# JLink_ARM-OB_072_Sch.net
KiCad netlist of a schematic drawn in Altium Designer
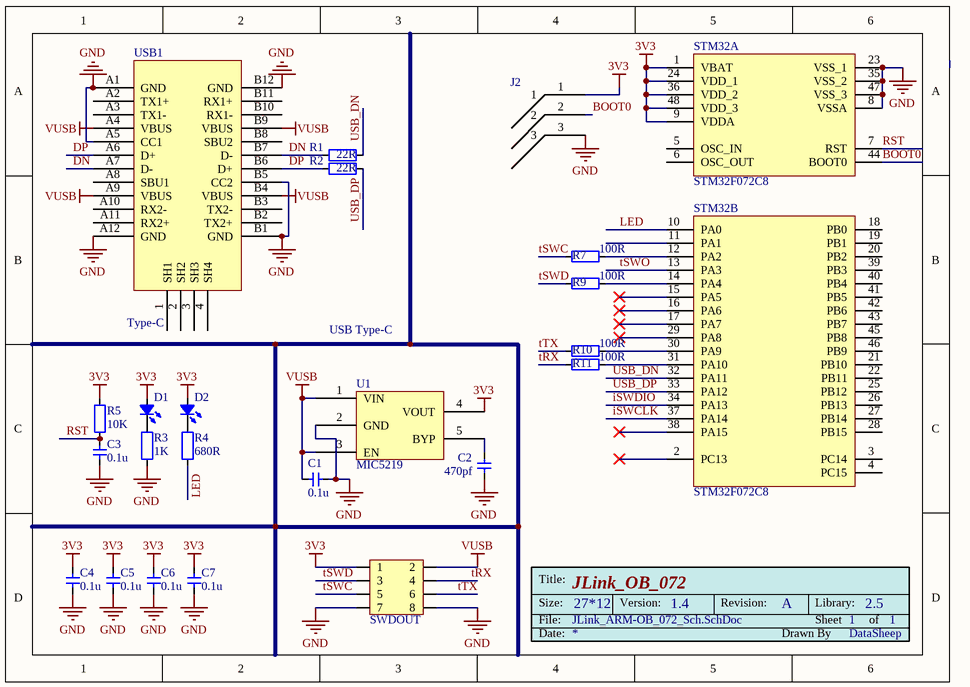
[diagram p0: JLink_ARM-OB_072_Sch.SchDoc]

(export (version "E")
  (design (tool "Eeschema 10.0.6"))
  (components
    (comp (ref "C1")
      (value "0.1u")
      (footprint "PCB_PassiveCap:CAP_0603")
      (description "Capacitor")
      (fields (field (name "Comment") "Cap_0603"))
      (libsource (lib "SCH_Passive") (part "Cap_0603"))
    )
    (comp (ref "C2")
      (value "470pf")
      (footprint "PCB_PassiveCap:CAP_0603")
      (description "Capacitor")
      (fields (field (name "Comment") "Cap_0603"))
      (libsource (lib "SCH_Passive") (part "Cap_0603"))
    )
    (comp (ref "C3")
      (value "0.1u")
      (footprint "PCB_PassiveCap:CAP_0603")
      (description "Capacitor")
      (fields (field (name "Comment") "Cap_0603"))
      (libsource (lib "SCH_Passive") (part "Cap_0603"))
    )
    (comp (ref "C4")
      (value "0.1u")
      (footprint "PCB_PassiveCap:CAP_0603")
      (description "Capacitor")
      (fields (field (name "Comment") "Cap_0603"))
      (libsource (lib "SCH_Passive") (part "Cap_0603"))
    )
    (comp (ref "C5")
      (value "0.1u")
      (footprint "PCB_PassiveCap:CAP_0603")
      (description "Capacitor")
      (fields (field (name "Comment") "Cap_0603"))
      (libsource (lib "SCH_Passive") (part "Cap_0603"))
    )
    (comp (ref "C6")
      (value "0.1u")
      (footprint "PCB_PassiveCap:CAP_0603")
      (description "Capacitor")
      (fields (field (name "Comment") "Cap_0603"))
      (libsource (lib "SCH_Passive") (part "Cap_0603"))
    )
    (comp (ref "C7")
      (value "0.1u")
      (footprint "PCB_PassiveCap:CAP_0603")
      (description "Capacitor")
      (fields (field (name "Comment") "Cap_0603"))
      (libsource (lib "SCH_Passive") (part "Cap_0603"))
    )
    (comp (ref "D1")
      (value "LED_0603")
      (footprint "0603/LED")
      (description "LED")
      (libsource (lib "SCH_Active") (part "LED_0603"))
    )
    (comp (ref "D2")
      (value "LED_0603")
      (footprint "0603/LED")
      (description "LED")
      (libsource (lib "SCH_Active") (part "LED_0603"))
    )
    (comp (ref "J2") (value "~") (footprint "test") (libsource (lib "PCB") (part "测试点")))
    (comp (ref "R1")
      (value "22R")
      (footprint "PCB_PassiveRes:RES_0603")
      (description "Resistor")
      (fields (field (name "Comment") "Res_0603"))
      (libsource (lib "") (part "Res_0603_1"))
    )
    (comp (ref "R2")
      (value "22R")
      (footprint "PCB_PassiveRes:RES_0603")
      (description "Resistor")
      (fields (field (name "Comment") "Res_0603"))
      (libsource (lib "") (part "Res_0603_1"))
    )
    (comp (ref "R3")
      (value "1K")
      (footprint "PCB_PassiveRes:RES_0603")
      (description "Resistor")
      (fields (field (name "Comment") "Res_0603"))
      (libsource (lib "SCH_Passive") (part "Res_0603"))
    )
    (comp (ref "R4")
      (value "680R")
      (footprint "PCB_PassiveRes:RES_0603")
      (description "Resistor")
      (fields (field (name "Comment") "Res_0603"))
      (libsource (lib "SCH_Passive") (part "Res_0603"))
    )
    (comp (ref "R5")
      (value "10K")
      (footprint "PCB_PassiveRes:RES_0603")
      (description "Resistor")
      (fields (field (name "Comment") "Res_0603"))
      (libsource (lib "SCH_Passive") (part "Res_0603"))
    )
    (comp (ref "R7")
      (value "100R")
      (footprint "PCB_PassiveRes:RES_0603")
      (description "Resistor")
      (fields (field (name "Comment") "Res_0603"))
      (libsource (lib "") (part "Res_0603_1"))
    )
    (comp (ref "R9")
      (value "100R")
      (footprint "PCB_PassiveRes:RES_0603")
      (description "Resistor")
      (fields (field (name "Comment") "Res_0603"))
      (libsource (lib "") (part "Res_0603_1"))
    )
    (comp (ref "R10")
      (value "100R")
      (footprint "PCB_PassiveRes:RES_0603")
      (description "Resistor")
      (fields (field (name "Comment") "Res_0603"))
      (libsource (lib "") (part "Res_0603_1"))
    )
    (comp (ref "R11")
      (value "100R")
      (footprint "PCB_PassiveRes:RES_0603")
      (description "Resistor")
      (fields (field (name "Comment") "Res_0603"))
      (libsource (lib "") (part "Res_0603_1"))
    )
    (comp (ref "STM32")
      (value "STM32F072C8")
      (footprint "PCB_IntegratedCircuit:LQFP_P0.5_48")
      (description "MCU")
      (libsource (lib "SCH_IntegratedCircuit") (part "STM32F103C"))
    )
    (comp (ref "SWDOUT")
      (value "HDR2x4_2.54")
      (footprint "PCB_ConnectorHDR:HDR2X4_2.54_180H")
      (description "Header")
      (libsource (lib "SCH_ConnectorHDR") (part "HDR2x4_2.54"))
    )
    (comp (ref "U1") (value "MIC5219") (footprint "SOT23-5") (libsource (lib "PCB") (part "MIC5219")))
    (comp (ref "USB1") (value "Type-C") (footprint "Type-C") (libsource (lib "元件") (part "Type-C")))
  )
  (nets
    (net (code "1") (name "/BOOT0") (class "Default")
      (node (ref "J2") (pin "2") (pinfunction "2_2") (pintype "passive"))
      (node (ref "STM32") (pin "44") (pinfunction "BOOT0_44") (pintype "passive"))
    )
    (net (code "2") (name "/DN") (class "Default")
      (node (ref "R1") (pin "1") (pinfunction "1_1") (pintype "passive"))
      (node (ref "USB1") (pin "A7") (pinfunction "D-_A7") (pintype "passive"))
      (node (ref "USB1") (pin "B7") (pinfunction "D-_B7") (pintype "passive"))
    )
    (net (code "3") (name "/DP") (class "Default")
      (node (ref "R2") (pin "1") (pinfunction "1_1") (pintype "passive"))
      (node (ref "USB1") (pin "A6") (pinfunction "D+_A6") (pintype "passive"))
      (node (ref "USB1") (pin "B6") (pinfunction "D+_B6") (pintype "passive"))
    )
    (net (code "4") (name "/LED") (class "Default")
      (node (ref "R4") (pin "1") (pinfunction "1_1") (pintype "passive"))
      (node (ref "STM32") (pin "10") (pinfunction "PA0_10") (pintype "passive"))
    )
    (net (code "5") (name "/RST") (class "Default")
      (node (ref "C3") (pin "2") (pinfunction "2_2") (pintype "passive"))
      (node (ref "R5") (pin "1") (pinfunction "1_1") (pintype "passive"))
      (node (ref "STM32") (pin "7") (pinfunction "RST_7") (pintype "passive"))
    )
    (net (code "6") (name "/USB_DN") (class "Default")
      (node (ref "R1") (pin "2") (pinfunction "2_2") (pintype "passive"))
      (node (ref "STM32") (pin "32") (pinfunction "PA11_32") (pintype "passive"))
    )
    (net (code "7") (name "/USB_DP") (class "Default")
      (node (ref "R2") (pin "2") (pinfunction "2_2") (pintype "passive"))
      (node (ref "STM32") (pin "33") (pinfunction "PA12_33") (pintype "passive"))
    )
    (net (code "8") (name "/iSWCLK") (class "Default")
      (node (ref "STM32") (pin "37") (pinfunction "PA14_37") (pintype "passive"))
    )
    (net (code "9") (name "/iSWDIO") (class "Default")
      (node (ref "STM32") (pin "34") (pinfunction "PA13_34") (pintype "passive"))
    )
    (net (code "10") (name "/tRX") (class "Default")
      (node (ref "R11") (pin "1") (pinfunction "1_1") (pintype "passive"))
      (node (ref "SWDOUT") (pin "4") (pinfunction "4_4") (pintype "passive"))
    )
    (net (code "11") (name "/tSWC") (class "Default")
      (node (ref "R7") (pin "1") (pinfunction "1_1") (pintype "passive"))
      (node (ref "SWDOUT") (pin "5") (pinfunction "5_5") (pintype "passive"))
    )
    (net (code "12") (name "/tSWD") (class "Default")
      (node (ref "R9") (pin "1") (pinfunction "1_1") (pintype "passive"))
      (node (ref "SWDOUT") (pin "3") (pinfunction "3_3") (pintype "passive"))
    )
    (net (code "13") (name "/tSWO") (class "Default")
      (node (ref "STM32") (pin "13") (pinfunction "PA3_13") (pintype "passive"))
    )
    (net (code "14") (name "/tTX") (class "Default")
      (node (ref "R10") (pin "1") (pinfunction "1_1") (pintype "passive"))
      (node (ref "SWDOUT") (pin "6") (pinfunction "6_6") (pintype "passive"))
    )
    (net (code "15") (name "3V3") (class "Default")
      (node (ref "C4") (pin "2") (pinfunction "2_2") (pintype "passive"))
      (node (ref "C5") (pin "2") (pinfunction "2_2") (pintype "passive"))
      (node (ref "C6") (pin "2") (pinfunction "2_2") (pintype "passive"))
      (node (ref "C7") (pin "2") (pinfunction "2_2") (pintype "passive"))
      (node (ref "D1") (pin "1") (pinfunction "A_1") (pintype "passive"))
      (node (ref "D2") (pin "1") (pinfunction "A_1") (pintype "passive"))
      (node (ref "J2") (pin "1") (pinfunction "1_1") (pintype "passive"))
      (node (ref "R5") (pin "2") (pinfunction "2_2") (pintype "passive"))
      (node (ref "STM32") (pin "1") (pinfunction "VBAT_1") (pintype "passive"))
      (node (ref "STM32") (pin "24") (pinfunction "VDD_1_24") (pintype "passive"))
      (node (ref "STM32") (pin "36") (pinfunction "VDD_2_36") (pintype "passive"))
      (node (ref "STM32") (pin "48") (pinfunction "VDD_3_48") (pintype "passive"))
      (node (ref "STM32") (pin "9") (pinfunction "VDDA_9") (pintype "passive"))
      (node (ref "SWDOUT") (pin "1") (pinfunction "1_1") (pintype "passive"))
      (node (ref "U1") (pin "4") (pinfunction "VOUT_4") (pintype "passive"))
    )
    (net (code "16") (name "GND") (class "Default")
      (node (ref "C1") (pin "1") (pinfunction "1_1") (pintype "passive"))
      (node (ref "C2") (pin "1") (pinfunction "1_1") (pintype "passive"))
      (node (ref "C3") (pin "1") (pinfunction "1_1") (pintype "passive"))
      (node (ref "C4") (pin "1") (pinfunction "1_1") (pintype "passive"))
      (node (ref "C5") (pin "1") (pinfunction "1_1") (pintype "passive"))
      (node (ref "C6") (pin "1") (pinfunction "1_1") (pintype "passive"))
      (node (ref "C7") (pin "1") (pinfunction "1_1") (pintype "passive"))
      (node (ref "J2") (pin "3") (pinfunction "3_3") (pintype "passive"))
      (node (ref "R3") (pin "1") (pinfunction "1_1") (pintype "passive"))
      (node (ref "STM32") (pin "23") (pinfunction "VSS_1_23") (pintype "passive"))
      (node (ref "STM32") (pin "35") (pinfunction "VSS_2_35") (pintype "passive"))
      (node (ref "STM32") (pin "47") (pinfunction "VSS_3_47") (pintype "passive"))
      (node (ref "STM32") (pin "8") (pinfunction "VSSA_8") (pintype "passive"))
      (node (ref "SWDOUT") (pin "7") (pinfunction "7_7") (pintype "passive"))
      (node (ref "SWDOUT") (pin "8") (pinfunction "8_8") (pintype "passive"))
      (node (ref "U1") (pin "2") (pinfunction "GND_2") (pintype "passive"))
      (node (ref "USB1") (pin "A1") (pinfunction "GND_A1") (pintype "passive"))
      (node (ref "USB1") (pin "A12") (pinfunction "GND_A12") (pintype "passive"))
      (node (ref "USB1") (pin "A5") (pinfunction "CC1_A5") (pintype "passive"))
      (node (ref "USB1") (pin "B1") (pinfunction "GND_B1") (pintype "passive"))
      (node (ref "USB1") (pin "B12") (pinfunction "GND_B12") (pintype "passive"))
      (node (ref "USB1") (pin "B5") (pinfunction "CC2_B5") (pintype "passive"))
    )
    (net (code "17") (name "Net-(D1-K)") (class "Default")
      (node (ref "D1") (pin "2") (pinfunction "K_2") (pintype "passive"))
      (node (ref "R3") (pin "2") (pinfunction "2_2") (pintype "passive"))
    )
    (net (code "18") (name "Net-(D2-K)") (class "Default")
      (node (ref "D2") (pin "2") (pinfunction "K_2") (pintype "passive"))
      (node (ref "R4") (pin "2") (pinfunction "2_2") (pintype "passive"))
    )
    (net (code "19") (name "Net-(STM32B-PA2)") (class "Default")
      (node (ref "R7") (pin "2") (pinfunction "2_2") (pintype "passive"))
      (node (ref "STM32") (pin "12") (pinfunction "PA2_12") (pintype "passive"))
    )
    (net (code "20") (name "Net-(STM32B-PA4)") (class "Default")
      (node (ref "R9") (pin "2") (pinfunction "2_2") (pintype "passive"))
      (node (ref "STM32") (pin "14") (pinfunction "PA4_14") (pintype "passive"))
    )
    (net (code "21") (name "Net-(STM32B-PA9)") (class "Default")
      (node (ref "R10") (pin "2") (pinfunction "2_2") (pintype "passive"))
      (node (ref "STM32") (pin "30") (pinfunction "PA9_30") (pintype "passive"))
    )
    (net (code "22") (name "Net-(STM32B-PA10)") (class "Default")
      (node (ref "R11") (pin "2") (pinfunction "2_2") (pintype "passive"))
      (node (ref "STM32") (pin "31") (pinfunction "PA10_31") (pintype "passive"))
    )
    (net (code "23") (name "Net-(U1-BYP)") (class "Default")
      (node (ref "C2") (pin "2") (pinfunction "2_2") (pintype "passive"))
      (node (ref "U1") (pin "5") (pinfunction "BYP_5") (pintype "passive"))
    )
    (net (code "24") (name "VUSB") (class "Default")
      (node (ref "C1") (pin "2") (pinfunction "2_2") (pintype "passive"))
      (node (ref "SWDOUT") (pin "2") (pinfunction "2_2") (pintype "passive"))
      (node (ref "U1") (pin "1") (pinfunction "VIN_1") (pintype "passive"))
      (node (ref "U1") (pin "3") (pinfunction "EN_3") (pintype "passive"))
      (node (ref "USB1") (pin "A4") (pinfunction "VBUS_A4") (pintype "passive"))
      (node (ref "USB1") (pin "A9") (pinfunction "VBUS_A9") (pintype "passive"))
      (node (ref "USB1") (pin "B4") (pinfunction "VBUS_B4") (pintype "passive"))
      (node (ref "USB1") (pin "B9") (pinfunction "VBUS_B9") (pintype "passive"))
    )
    (net (code "25") (name "unconnected-(STM32A-OSC_IN-Pad5)") (class "Default")
      (node (ref "STM32") (pin "5") (pinfunction "OSC_IN_5") (pintype "passive"))
    )
    (net (code "26") (name "unconnected-(STM32A-OSC_OUT-Pad6)") (class "Default")
      (node (ref "STM32") (pin "6") (pinfunction "OSC_OUT_6") (pintype "passive"))
    )
    (net (code "27") (name "unconnected-(STM32B-PA1-Pad11)") (class "Default")
      (node (ref "STM32") (pin "11") (pinfunction "PA1_11") (pintype "passive"))
    )
    (net (code "28") (name "unconnected-(STM32B-PA5-Pad15)") (class "Default")
      (node (ref "STM32") (pin "15") (pinfunction "PA5_15") (pintype "passive+no_connect"))
    )
    (net (code "29") (name "unconnected-(STM32B-PA6-Pad16)") (class "Default")
      (node (ref "STM32") (pin "16") (pinfunction "PA6_16") (pintype "passive+no_connect"))
    )
    (net (code "30") (name "unconnected-(STM32B-PA7-Pad17)") (class "Default")
      (node (ref "STM32") (pin "17") (pinfunction "PA7_17") (pintype "passive+no_connect"))
    )
    (net (code "31") (name "unconnected-(STM32B-PA8-Pad29)") (class "Default")
      (node (ref "STM32") (pin "29") (pinfunction "PA8_29") (pintype "passive+no_connect"))
    )
    (net (code "32") (name "unconnected-(STM32B-PA15-Pad38)") (class "Default")
      (node (ref "STM32") (pin "38") (pinfunction "PA15_38") (pintype "passive+no_connect"))
    )
    (net (code "33") (name "unconnected-(STM32B-PB0-Pad18)") (class "Default")
      (node (ref "STM32") (pin "18") (pinfunction "PB0_18") (pintype "passive"))
    )
    (net (code "34") (name "unconnected-(STM32B-PB1-Pad19)") (class "Default")
      (node (ref "STM32") (pin "19") (pinfunction "PB1_19") (pintype "passive"))
    )
    (net (code "35") (name "unconnected-(STM32B-PB2-Pad20)") (class "Default")
      (node (ref "STM32") (pin "20") (pinfunction "PB2_20") (pintype "passive"))
    )
    (net (code "36") (name "unconnected-(STM32B-PB3-Pad39)") (class "Default")
      (node (ref "STM32") (pin "39") (pinfunction "PB3_39") (pintype "passive"))
    )
    (net (code "37") (name "unconnected-(STM32B-PB4-Pad40)") (class "Default")
      (node (ref "STM32") (pin "40") (pinfunction "PB4_40") (pintype "passive"))
    )
    (net (code "38") (name "unconnected-(STM32B-PB5-Pad41)") (class "Default")
      (node (ref "STM32") (pin "41") (pinfunction "PB5_41") (pintype "passive"))
    )
    (net (code "39") (name "unconnected-(STM32B-PB6-Pad42)") (class "Default")
      (node (ref "STM32") (pin "42") (pinfunction "PB6_42") (pintype "passive"))
    )
    (net (code "40") (name "unconnected-(STM32B-PB7-Pad43)") (class "Default")
      (node (ref "STM32") (pin "43") (pinfunction "PB7_43") (pintype "passive"))
    )
    (net (code "41") (name "unconnected-(STM32B-PB8-Pad45)") (class "Default")
      (node (ref "STM32") (pin "45") (pinfunction "PB8_45") (pintype "passive"))
    )
    (net (code "42") (name "unconnected-(STM32B-PB9-Pad46)") (class "Default")
      (node (ref "STM32") (pin "46") (pinfunction "PB9_46") (pintype "passive"))
    )
    (net (code "43") (name "unconnected-(STM32B-PB10-Pad21)") (class "Default")
      (node (ref "STM32") (pin "21") (pinfunction "PB10_21") (pintype "passive"))
    )
    (net (code "44") (name "unconnected-(STM32B-PB11-Pad22)") (class "Default")
      (node (ref "STM32") (pin "22") (pinfunction "PB11_22") (pintype "passive"))
    )
    (net (code "45") (name "unconnected-(STM32B-PB12-Pad25)") (class "Default")
      (node (ref "STM32") (pin "25") (pinfunction "PB12_25") (pintype "passive"))
    )
    (net (code "46") (name "unconnected-(STM32B-PB13-Pad26)") (class "Default")
      (node (ref "STM32") (pin "26") (pinfunction "PB13_26") (pintype "passive"))
    )
    (net (code "47") (name "unconnected-(STM32B-PB14-Pad27)") (class "Default")
      (node (ref "STM32") (pin "27") (pinfunction "PB14_27") (pintype "passive"))
    )
    (net (code "48") (name "unconnected-(STM32B-PB15-Pad28)") (class "Default")
      (node (ref "STM32") (pin "28") (pinfunction "PB15_28") (pintype "passive"))
    )
    (net (code "49") (name "unconnected-(STM32B-PC13-Pad2)") (class "Default")
      (node (ref "STM32") (pin "2") (pinfunction "PC13_2") (pintype "passive+no_connect"))
    )
    (net (code "50") (name "unconnected-(STM32B-PC14-Pad3)") (class "Default")
      (node (ref "STM32") (pin "3") (pinfunction "PC14_3") (pintype "passive"))
    )
    (net (code "51") (name "unconnected-(STM32B-PC15-Pad4)") (class "Default")
      (node (ref "STM32") (pin "4") (pinfunction "PC15_4") (pintype "passive"))
    )
    (net (code "52") (name "unconnected-(USB1-RX1+-PadB11)") (class "Default")
      (node (ref "USB1") (pin "B11") (pinfunction "RX1+_B11") (pintype "passive"))
    )
    (net (code "53") (name "unconnected-(USB1-RX1--PadB10)") (class "Default")
      (node (ref "USB1") (pin "B10") (pinfunction "RX1-_B10") (pintype "passive"))
    )
    (net (code "54") (name "unconnected-(USB1-RX2+-PadA11)") (class "Default")
      (node (ref "USB1") (pin "A11") (pinfunction "RX2+_A11") (pintype "passive"))
    )
    (net (code "55") (name "unconnected-(USB1-RX2--PadA10)") (class "Default")
      (node (ref "USB1") (pin "A10") (pinfunction "RX2-_A10") (pintype "passive"))
    )
    (net (code "56") (name "unconnected-(USB1-SBU1-PadA8)") (class "Default")
      (node (ref "USB1") (pin "A8") (pinfunction "SBU1_A8") (pintype "passive"))
    )
    (net (code "57") (name "unconnected-(USB1-SBU2-PadB8)") (class "Default")
      (node (ref "USB1") (pin "B8") (pinfunction "SBU2_B8") (pintype "passive"))
    )
    (net (code "58") (name "unconnected-(USB1-SH1-Pad1)") (class "Default")
      (node (ref "USB1") (pin "1") (pinfunction "SH1_1") (pintype "passive"))
    )
    (net (code "59") (name "unconnected-(USB1-SH2-Pad2)") (class "Default")
      (node (ref "USB1") (pin "2") (pinfunction "SH2_2") (pintype "passive"))
    )
    (net (code "60") (name "unconnected-(USB1-SH3-Pad3)") (class "Default")
      (node (ref "USB1") (pin "3") (pinfunction "SH3_3") (pintype "passive"))
    )
    (net (code "61") (name "unconnected-(USB1-SH4-Pad4)") (class "Default")
      (node (ref "USB1") (pin "4") (pinfunction "SH4_4") (pintype "passive"))
    )
    (net (code "62") (name "unconnected-(USB1-TX1+-PadA2)") (class "Default")
      (node (ref "USB1") (pin "A2") (pinfunction "TX1+_A2") (pintype "passive"))
    )
    (net (code "63") (name "unconnected-(USB1-TX1--PadA3)") (class "Default")
      (node (ref "USB1") (pin "A3") (pinfunction "TX1-_A3") (pintype "passive"))
    )
    (net (code "64") (name "unconnected-(USB1-TX2+-PadB2)") (class "Default")
      (node (ref "USB1") (pin "B2") (pinfunction "TX2+_B2") (pintype "passive"))
    )
    (net (code "65") (name "unconnected-(USB1-TX2--PadB3)") (class "Default")
      (node (ref "USB1") (pin "B3") (pinfunction "TX2-_B3") (pintype "passive"))
    )
  )
)
